# 25_-_LEDS_BUTTONS.net
KiCad netlist of a schematic drawn in Altium Designer
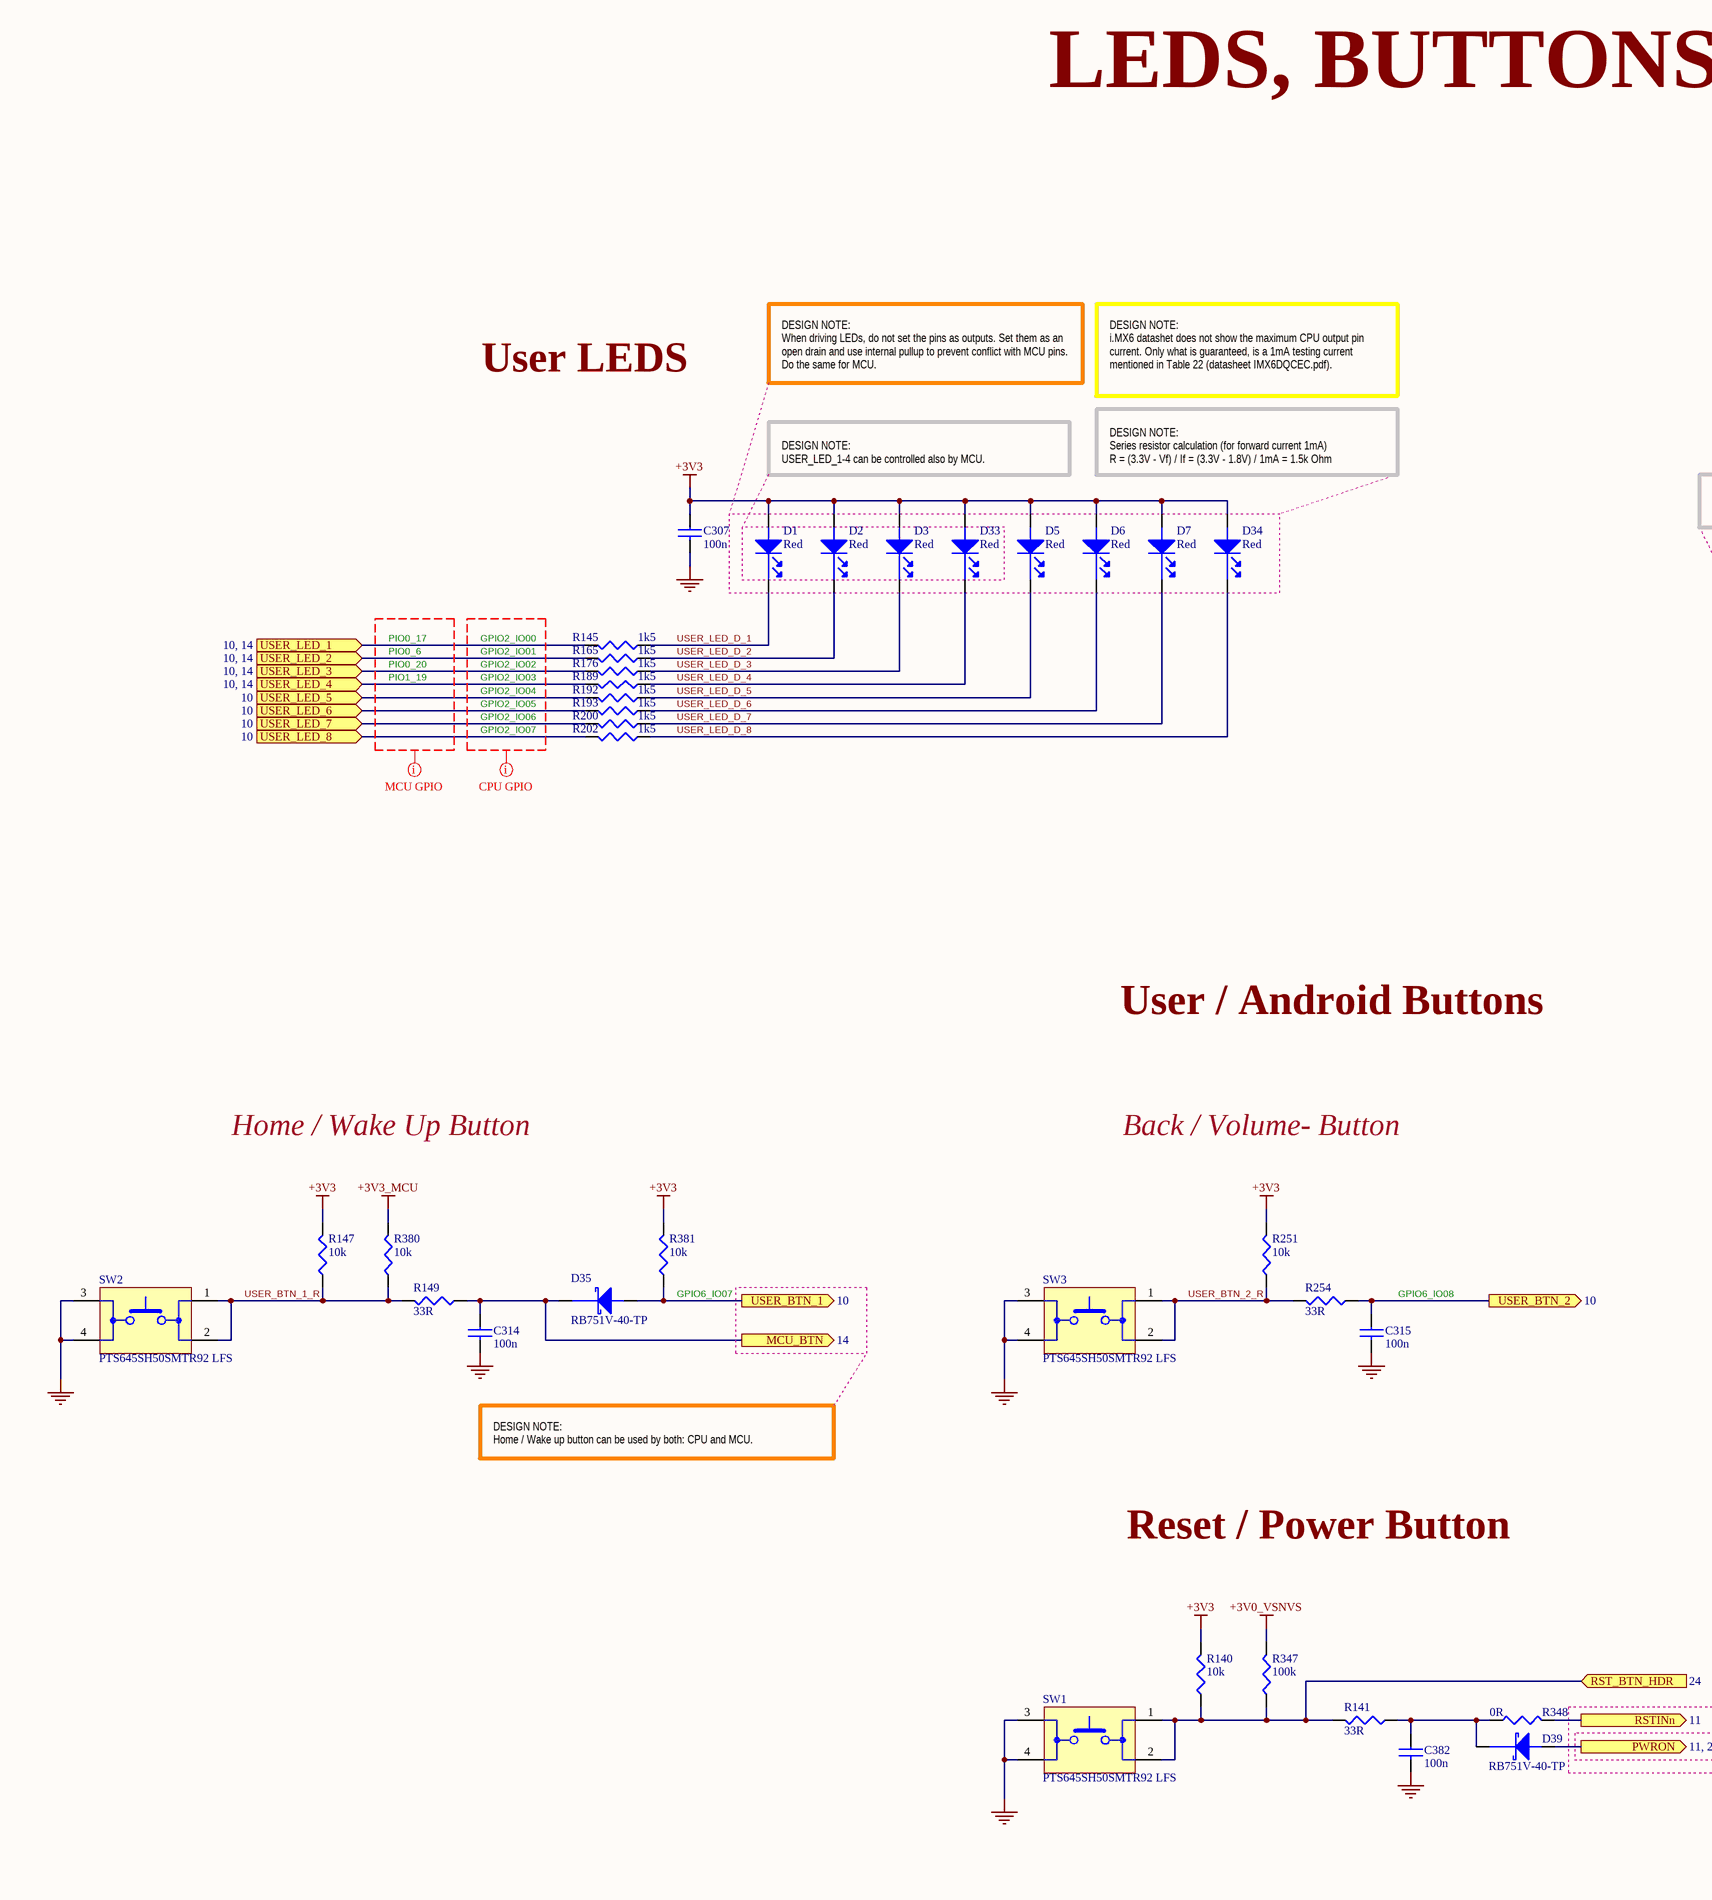
[diagram p0: [25] - LEDS, BUTTONS.SchDoc, left]
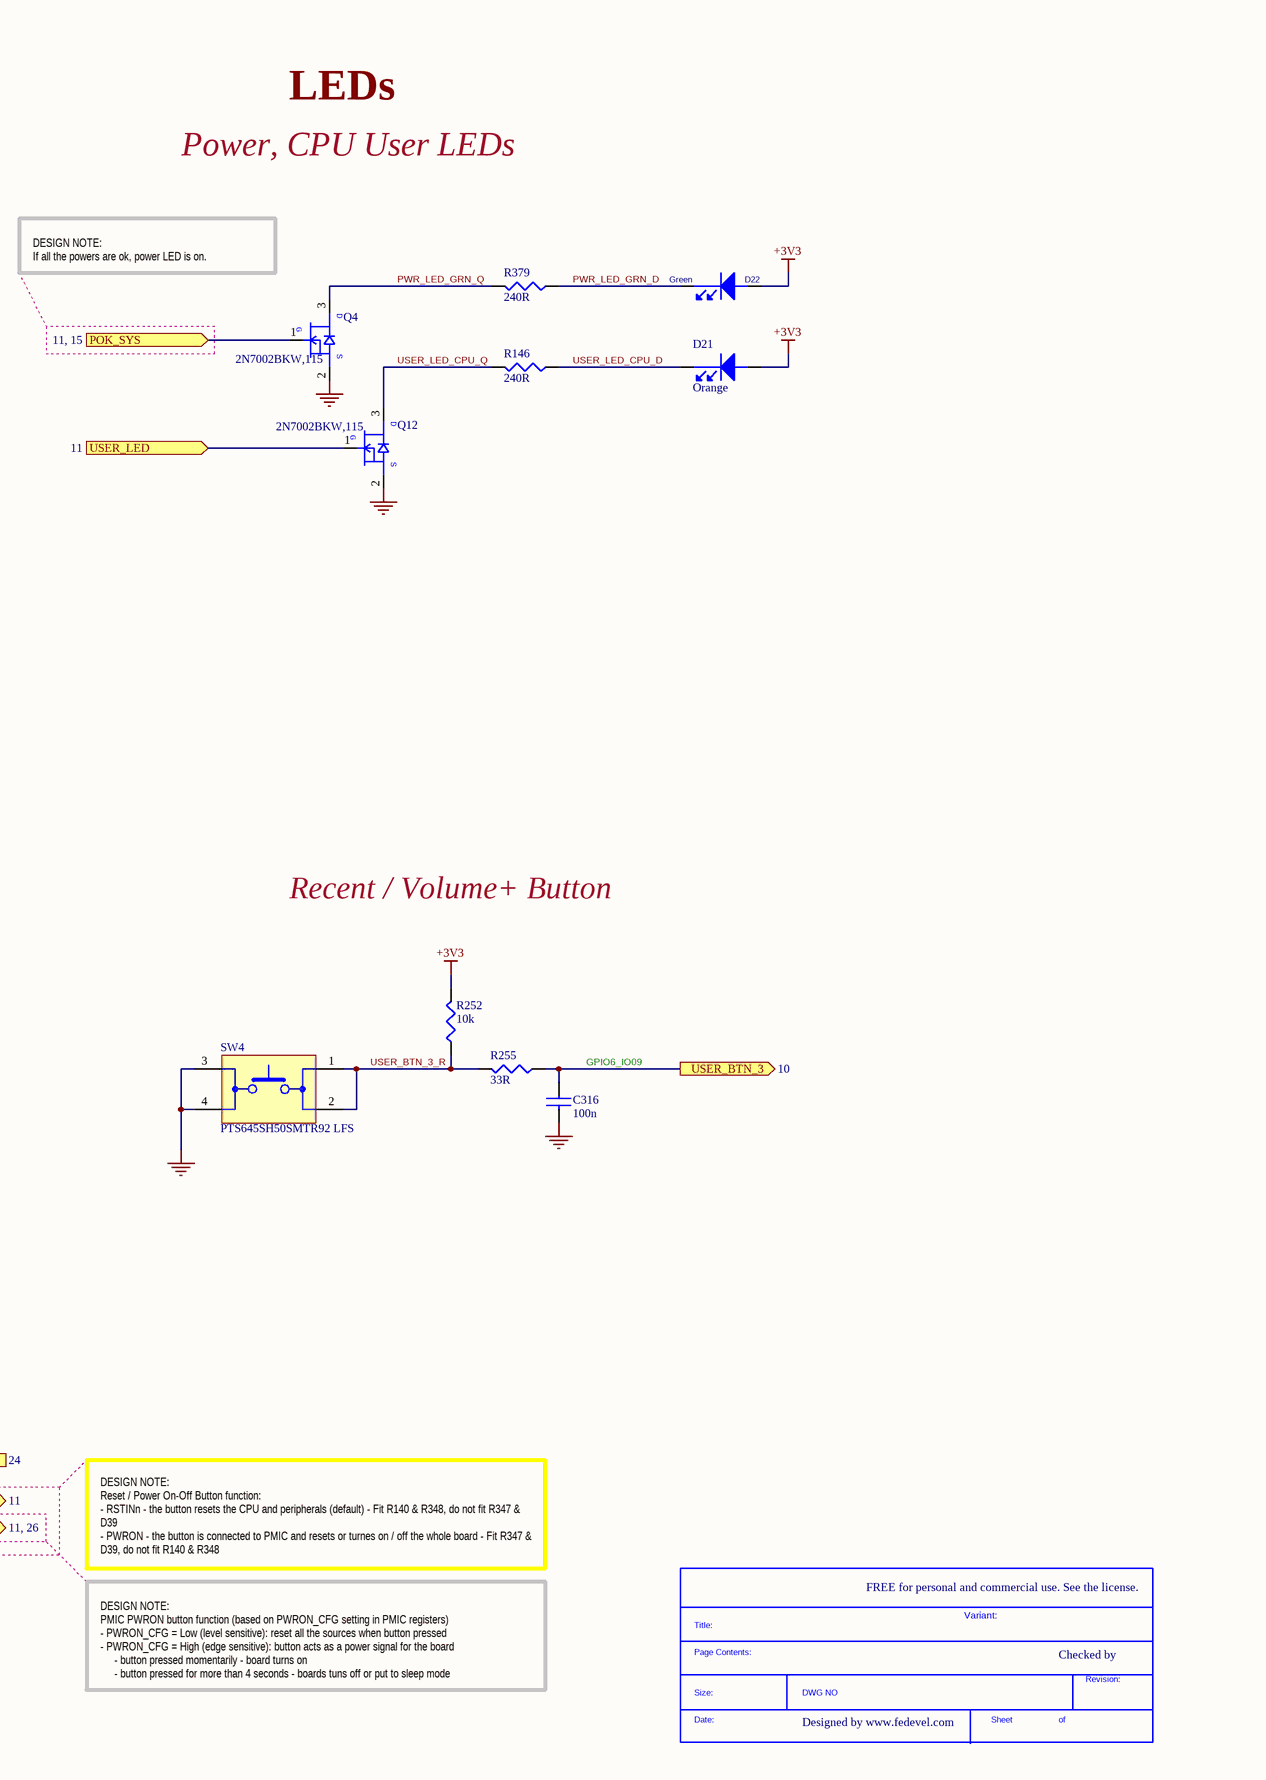
[diagram p1: [25] - LEDS, BUTTONS.SchDoc, right]

(export (version "E")
  (design (tool "Eeschema 10.0.6"))
  (components
    (comp (ref "C307")
      (value "100n")
      (footprint "C0402")
      (description "CAP CER .10UF 50V X5R 10% 0402")
      (fields
        (field (name "MANUFACTURER") "TDK Corporation")
        (field (name "MANUFACTURER PART NUMBER") "C1005X5R1H104K")
      )
      (libsource (lib "Integrated_Library_FEDEVEL_APR_2015") (part "C1005X5R1H104K"))
    )
    (comp (ref "C314")
      (value "100n")
      (footprint "C0402")
      (description "CAP CER .10UF 50V X5R 10% 0402")
      (fields
        (field (name "MANUFACTURER") "TDK Corporation")
        (field (name "MANUFACTURER PART NUMBER") "C1005X5R1H104K")
      )
      (libsource (lib "Integrated_Library_FEDEVEL_APR_2015") (part "C1005X5R1H104K"))
    )
    (comp (ref "C315")
      (value "100n")
      (footprint "C0402")
      (description "CAP CER .10UF 50V X5R 10% 0402")
      (fields
        (field (name "MANUFACTURER") "TDK Corporation")
        (field (name "MANUFACTURER PART NUMBER") "C1005X5R1H104K")
      )
      (libsource (lib "Integrated_Library_FEDEVEL_APR_2015") (part "C1005X5R1H104K"))
    )
    (comp (ref "C316")
      (value "100n")
      (footprint "C0402")
      (description "CAP CER .10UF 50V X5R 10% 0402")
      (fields
        (field (name "MANUFACTURER") "TDK Corporation")
        (field (name "MANUFACTURER PART NUMBER") "C1005X5R1H104K")
      )
      (libsource (lib "Integrated_Library_FEDEVEL_APR_2015") (part "C1005X5R1H104K"))
    )
    (comp (ref "C382")
      (value "100n")
      (footprint "C0402")
      (description "CAP CER .10UF 50V X5R 10% 0402")
      (fields
        (field (name "MANUFACTURER") "TDK Corporation")
        (field (name "MANUFACTURER PART NUMBER") "C1005X5R1H104K")
      )
      (libsource (lib "Integrated_Library_FEDEVEL_APR_2015") (part "C1005X5R1H104K"))
    )
    (comp (ref "D1")
      (value "Red")
      (footprint "LED_0603")
      (description "LED SMARTLED RED 630NM 0603 SMD")
      (fields
        (field (name "MANUFACTURER") "OSRAM Opto Semiconductors Inc")
        (field (name "MANUFACTURER PART NUMBER") "LS L29K-H1J2-1-Z")
      )
      (libsource (lib "Integrated_Library_FEDEVEL_APR_2015") (part "LS L29K-H1J2-1-Z"))
    )
    (comp (ref "D2")
      (value "Red")
      (footprint "LED_0603")
      (description "LED SMARTLED RED 630NM 0603 SMD")
      (fields
        (field (name "MANUFACTURER") "OSRAM Opto Semiconductors Inc")
        (field (name "MANUFACTURER PART NUMBER") "LS L29K-H1J2-1-Z")
      )
      (libsource (lib "Integrated_Library_FEDEVEL_APR_2015") (part "LS L29K-H1J2-1-Z"))
    )
    (comp (ref "D3")
      (value "Red")
      (footprint "LED_0603")
      (description "LED SMARTLED RED 630NM 0603 SMD")
      (fields
        (field (name "MANUFACTURER") "OSRAM Opto Semiconductors Inc")
        (field (name "MANUFACTURER PART NUMBER") "LS L29K-H1J2-1-Z")
      )
      (libsource (lib "Integrated_Library_FEDEVEL_APR_2015") (part "LS L29K-H1J2-1-Z"))
    )
    (comp (ref "D5")
      (value "Red")
      (footprint "LED_0603")
      (description "LED SMARTLED RED 630NM 0603 SMD")
      (fields
        (field (name "MANUFACTURER") "OSRAM Opto Semiconductors Inc")
        (field (name "MANUFACTURER PART NUMBER") "LS L29K-H1J2-1-Z")
      )
      (libsource (lib "Integrated_Library_FEDEVEL_APR_2015") (part "LS L29K-H1J2-1-Z"))
    )
    (comp (ref "D6")
      (value "Red")
      (footprint "LED_0603")
      (description "LED SMARTLED RED 630NM 0603 SMD")
      (fields
        (field (name "MANUFACTURER") "OSRAM Opto Semiconductors Inc")
        (field (name "MANUFACTURER PART NUMBER") "LS L29K-H1J2-1-Z")
      )
      (libsource (lib "Integrated_Library_FEDEVEL_APR_2015") (part "LS L29K-H1J2-1-Z"))
    )
    (comp (ref "D7")
      (value "Red")
      (footprint "LED_0603")
      (description "LED SMARTLED RED 630NM 0603 SMD")
      (fields
        (field (name "MANUFACTURER") "OSRAM Opto Semiconductors Inc")
        (field (name "MANUFACTURER PART NUMBER") "LS L29K-H1J2-1-Z")
      )
      (libsource (lib "Integrated_Library_FEDEVEL_APR_2015") (part "LS L29K-H1J2-1-Z"))
    )
    (comp (ref "D21")
      (value "Orange")
      (footprint "LED_0603")
      (description "LED SMARTLED ORANGE 606NM 0603")
      (fields
        (field (name "MANUFACTURER") "OSRAM Opto Semiconductors Inc")
        (field (name "MANUFACTURER PART NUMBER") "LO L29K-H2K1-24-Z")
      )
      (libsource (lib "Integrated_Library_FEDEVEL_APR_2015") (part "LO L29K-H2K1-24-Z"))
    )
    (comp (ref "D22")
      (value "Green")
      (footprint "LED_0603")
      (description "LED SMARTLED GREEN 570NM 0603")
      (fields
        (field (name "MANUFACTURER") "OSRAM Opto Semiconductors Inc")
        (field (name "MANUFACTURER PART NUMBER") "LG L29K-G2J1-24-Z")
      )
      (libsource (lib "Integrated_Library_FEDEVEL_APR_2015") (part "LG L29K-G2J1-24-Z"))
    )
    (comp (ref "D33")
      (value "Red")
      (footprint "LED_0603")
      (description "LED SMARTLED RED 630NM 0603 SMD")
      (fields
        (field (name "MANUFACTURER") "OSRAM Opto Semiconductors Inc")
        (field (name "MANUFACTURER PART NUMBER") "LS L29K-H1J2-1-Z")
      )
      (libsource (lib "Integrated_Library_FEDEVEL_APR_2015") (part "LS L29K-H1J2-1-Z"))
    )
    (comp (ref "D34")
      (value "Red")
      (footprint "LED_0603")
      (description "LED SMARTLED RED 630NM 0603 SMD")
      (fields
        (field (name "MANUFACTURER") "OSRAM Opto Semiconductors Inc")
        (field (name "MANUFACTURER PART NUMBER") "LS L29K-H1J2-1-Z")
      )
      (libsource (lib "Integrated_Library_FEDEVEL_APR_2015") (part "LS L29K-H1J2-1-Z"))
    )
    (comp (ref "D35")
      (value "RB751V-40-TP")
      (footprint "SOD323")
      (description "DIODE SCHTKY 30MA 30V SOD-323")
      (fields (field (name "MANUFACTURER") "Micro Commercial Co"))
      (libsource (lib "Integrated_Library_FEDEVEL_APR_2015") (part "RB751V-40-TP"))
    )
    (comp (ref "D39")
      (value "RB751V-40-TP")
      (footprint "SOD323")
      (description "DIODE SCHTKY 30MA 30V SOD-323")
      (fields (field (name "MANUFACTURER") "Micro Commercial Co"))
      (libsource (lib "Integrated_Library_FEDEVEL_APR_2015") (part "RB751V-40-TP"))
    )
    (comp (ref "Q4")
      (value "2N7002BKW,115")
      (footprint "SC70_SOT323")
      (description "MOSFET N-CH 60V 310MA SOT323")
      (fields (field (name "MANUFACTURER") "NXP Semiconductors"))
      (libsource (lib "Integrated_Library_FEDEVEL_APR_2015") (part "2N7002BKW,115"))
    )
    (comp (ref "Q12")
      (value "2N7002BKW,115")
      (footprint "SC70_SOT323")
      (description "MOSFET N-CH 60V 310MA SOT323")
      (fields (field (name "MANUFACTURER") "NXP Semiconductors"))
      (libsource (lib "Integrated_Library_FEDEVEL_APR_2015") (part "2N7002BKW,115"))
    )
    (comp (ref "R140")
      (value "10k")
      (footprint "R0402")
      (description "RES 10.0K OHM 1/16W 1% 0402 SMD")
      (fields
        (field (name "MANUFACTURER") "Yageo")
        (field (name "MANUFACTURER PART NUMBER") "RC0402FR-0710KL")
      )
      (libsource (lib "Integrated_Library_FEDEVEL_APR_2015") (part "RC0402FR-0710KL"))
    )
    (comp (ref "R141")
      (value "33R")
      (footprint "R0402")
      (description "RES TF 33 OHM 1% 1/16W 0402")
      (fields
        (field (name "MANUFACTURER") "Stackpole Electronics Inc")
        (field (name "MANUFACTURER PART NUMBER") "RMCF0402FT33R0")
      )
      (libsource (lib "Integrated_Library_FEDEVEL_APR_2015") (part "RMCF0402FT33R0"))
    )
    (comp (ref "R145")
      (value "1k5")
      (footprint "R0402")
      (description "RES 1.50K OHM 1/16W 1% 0402 SMD")
      (fields
        (field (name "MANUFACTURER") "Yageo")
        (field (name "MANUFACTURER PART NUMBER") "RC0402FR-071K5L")
        (field (name ".CREATOR") "MM")
        (field (name ".CHECKED PCB") "MM")
        (field (name ".CHECKED SCH") "MM")
      )
      (libsource (lib "Integrated_Library_FEDEVEL_APR_2015") (part "RC0402FR-071K5L"))
    )
    (comp (ref "R146")
      (value "240R")
      (footprint "R0402")
      (description "RES TF 240 OHM 1% 0.0625W 0402")
      (fields
        (field (name "MANUFACTURER") "Stackpole Electronics Inc")
        (field (name "MANUFACTURER PART NUMBER") "RMCF0402FT240R")
      )
      (libsource (lib "Integrated_Library_FEDEVEL_APR_2015") (part "RMCF0402FT240R"))
    )
    (comp (ref "R147")
      (value "10k")
      (footprint "R0402")
      (description "RES 10.0K OHM 1/16W 1% 0402 SMD")
      (fields
        (field (name "MANUFACTURER") "Yageo")
        (field (name "MANUFACTURER PART NUMBER") "RC0402FR-0710KL")
      )
      (libsource (lib "Integrated_Library_FEDEVEL_APR_2015") (part "RC0402FR-0710KL"))
    )
    (comp (ref "R149")
      (value "33R")
      (footprint "R0402")
      (description "RES TF 33 OHM 1% 1/16W 0402")
      (fields
        (field (name "MANUFACTURER") "Stackpole Electronics Inc")
        (field (name "MANUFACTURER PART NUMBER") "RMCF0402FT33R0")
      )
      (libsource (lib "Integrated_Library_FEDEVEL_APR_2015") (part "RMCF0402FT33R0"))
    )
    (comp (ref "R165")
      (value "1k5")
      (footprint "R0402")
      (description "RES 1.50K OHM 1/16W 1% 0402 SMD")
      (fields
        (field (name "MANUFACTURER") "Yageo")
        (field (name "MANUFACTURER PART NUMBER") "RC0402FR-071K5L")
        (field (name ".CREATOR") "MM")
        (field (name ".CHECKED PCB") "MM")
        (field (name ".CHECKED SCH") "MM")
      )
      (libsource (lib "Integrated_Library_FEDEVEL_APR_2015") (part "RC0402FR-071K5L"))
    )
    (comp (ref "R176")
      (value "1k5")
      (footprint "R0402")
      (description "RES 1.50K OHM 1/16W 1% 0402 SMD")
      (fields
        (field (name "MANUFACTURER") "Yageo")
        (field (name "MANUFACTURER PART NUMBER") "RC0402FR-071K5L")
        (field (name ".CREATOR") "MM")
        (field (name ".CHECKED PCB") "MM")
        (field (name ".CHECKED SCH") "MM")
      )
      (libsource (lib "Integrated_Library_FEDEVEL_APR_2015") (part "RC0402FR-071K5L"))
    )
    (comp (ref "R189")
      (value "1k5")
      (footprint "R0402")
      (description "RES 1.50K OHM 1/16W 1% 0402 SMD")
      (fields
        (field (name "MANUFACTURER") "Yageo")
        (field (name "MANUFACTURER PART NUMBER") "RC0402FR-071K5L")
        (field (name ".CREATOR") "MM")
        (field (name ".CHECKED PCB") "MM")
        (field (name ".CHECKED SCH") "MM")
      )
      (libsource (lib "Integrated_Library_FEDEVEL_APR_2015") (part "RC0402FR-071K5L"))
    )
    (comp (ref "R192")
      (value "1k5")
      (footprint "R0402")
      (description "RES 1.50K OHM 1/16W 1% 0402 SMD")
      (fields
        (field (name "MANUFACTURER") "Yageo")
        (field (name "MANUFACTURER PART NUMBER") "RC0402FR-071K5L")
        (field (name ".CREATOR") "MM")
        (field (name ".CHECKED PCB") "MM")
        (field (name ".CHECKED SCH") "MM")
      )
      (libsource (lib "Integrated_Library_FEDEVEL_APR_2015") (part "RC0402FR-071K5L"))
    )
    (comp (ref "R193")
      (value "1k5")
      (footprint "R0402")
      (description "RES 1.50K OHM 1/16W 1% 0402 SMD")
      (fields
        (field (name "MANUFACTURER") "Yageo")
        (field (name "MANUFACTURER PART NUMBER") "RC0402FR-071K5L")
        (field (name ".CREATOR") "MM")
        (field (name ".CHECKED PCB") "MM")
        (field (name ".CHECKED SCH") "MM")
      )
      (libsource (lib "Integrated_Library_FEDEVEL_APR_2015") (part "RC0402FR-071K5L"))
    )
    (comp (ref "R200")
      (value "1k5")
      (footprint "R0402")
      (description "RES 1.50K OHM 1/16W 1% 0402 SMD")
      (fields
        (field (name "MANUFACTURER") "Yageo")
        (field (name "MANUFACTURER PART NUMBER") "RC0402FR-071K5L")
        (field (name ".CREATOR") "MM")
        (field (name ".CHECKED PCB") "MM")
        (field (name ".CHECKED SCH") "MM")
      )
      (libsource (lib "Integrated_Library_FEDEVEL_APR_2015") (part "RC0402FR-071K5L"))
    )
    (comp (ref "R202")
      (value "1k5")
      (footprint "R0402")
      (description "RES 1.50K OHM 1/16W 1% 0402 SMD")
      (fields
        (field (name "MANUFACTURER") "Yageo")
        (field (name "MANUFACTURER PART NUMBER") "RC0402FR-071K5L")
        (field (name ".CREATOR") "MM")
        (field (name ".CHECKED PCB") "MM")
        (field (name ".CHECKED SCH") "MM")
      )
      (libsource (lib "Integrated_Library_FEDEVEL_APR_2015") (part "RC0402FR-071K5L"))
    )
    (comp (ref "R251")
      (value "10k")
      (footprint "R0402")
      (description "RES 10.0K OHM 1/16W 1% 0402 SMD")
      (fields
        (field (name "MANUFACTURER") "Yageo")
        (field (name "MANUFACTURER PART NUMBER") "RC0402FR-0710KL")
      )
      (libsource (lib "Integrated_Library_FEDEVEL_APR_2015") (part "RC0402FR-0710KL"))
    )
    (comp (ref "R252")
      (value "10k")
      (footprint "R0402")
      (description "RES 10.0K OHM 1/16W 1% 0402 SMD")
      (fields
        (field (name "MANUFACTURER") "Yageo")
        (field (name "MANUFACTURER PART NUMBER") "RC0402FR-0710KL")
      )
      (libsource (lib "Integrated_Library_FEDEVEL_APR_2015") (part "RC0402FR-0710KL"))
    )
    (comp (ref "R254")
      (value "33R")
      (footprint "R0402")
      (description "RES TF 33 OHM 1% 1/16W 0402")
      (fields
        (field (name "MANUFACTURER") "Stackpole Electronics Inc")
        (field (name "MANUFACTURER PART NUMBER") "RMCF0402FT33R0")
      )
      (libsource (lib "Integrated_Library_FEDEVEL_APR_2015") (part "RMCF0402FT33R0"))
    )
    (comp (ref "R255")
      (value "33R")
      (footprint "R0402")
      (description "RES TF 33 OHM 1% 1/16W 0402")
      (fields
        (field (name "MANUFACTURER") "Stackpole Electronics Inc")
        (field (name "MANUFACTURER PART NUMBER") "RMCF0402FT33R0")
      )
      (libsource (lib "Integrated_Library_FEDEVEL_APR_2015") (part "RMCF0402FT33R0"))
    )
    (comp (ref "R347")
      (value "100k")
      (footprint "R0402")
      (description "RES 100K OHM 1/16W 1% 0402 SMD")
      (fields
        (field (name "MANUFACTURER") "Stackpole Electronics Inc")
        (field (name "MANUFACTURER PART NUMBER") "RMCF0402FT100K")
      )
      (libsource (lib "Integrated_Library_FEDEVEL_APR_2015") (part "RMCF0402FT100K"))
    )
    (comp (ref "R348")
      (value "0R")
      (footprint "R0402")
      (description "RES 0.0 OHM 1/16W 0402 SMD")
      (fields
        (field (name "MANUFACTURER") "Yageo")
        (field (name "MANUFACTURER PART NUMBER") "RC0402JR-070RL")
      )
      (libsource (lib "Integrated_Library_FEDEVEL_APR_2015") (part "RC0402JR-070RL"))
    )
    (comp (ref "R379")
      (value "240R")
      (footprint "R0402")
      (description "RES TF 240 OHM 1% 0.0625W 0402")
      (fields
        (field (name "MANUFACTURER") "Stackpole Electronics Inc")
        (field (name "MANUFACTURER PART NUMBER") "RMCF0402FT240R")
      )
      (libsource (lib "Integrated_Library_FEDEVEL_APR_2015") (part "RMCF0402FT240R"))
    )
    (comp (ref "R380")
      (value "10k")
      (footprint "R0402")
      (description "RES 10.0K OHM 1/16W 1% 0402 SMD")
      (fields
        (field (name "MANUFACTURER") "Yageo")
        (field (name "MANUFACTURER PART NUMBER") "RC0402FR-0710KL")
      )
      (libsource (lib "Integrated_Library_FEDEVEL_APR_2015") (part "RC0402FR-0710KL"))
    )
    (comp (ref "R381")
      (value "10k")
      (footprint "R0402")
      (description "RES 10.0K OHM 1/16W 1% 0402 SMD")
      (fields
        (field (name "MANUFACTURER") "Yageo")
        (field (name "MANUFACTURER PART NUMBER") "RC0402FR-0710KL")
      )
      (libsource (lib "Integrated_Library_FEDEVEL_APR_2015") (part "RC0402FR-0710KL"))
    )
    (comp (ref "SW1")
      (value "PTS645SH50SMTR92 LFS")
      (footprint "TACT_SMD")
      (description "SWITCH TACTILE SPST-NO 0.05A 12V")
      (fields
        (field (name "MANUFACTURER") "C&K Components")
        (field (name ".CHECKED PCB") "MM")
        (field (name ".CHECKED SCH") "MM")
        (field (name ".CREATOR") "MM")
      )
      (libsource (lib "Integrated_Library_FEDEVEL_APR_2015") (part "PTS645SH50SMTR92 LFS"))
    )
    (comp (ref "SW2")
      (value "PTS645SH50SMTR92 LFS")
      (footprint "TACT_SMD")
      (description "SWITCH TACTILE SPST-NO 0.05A 12V")
      (fields
        (field (name "MANUFACTURER") "C&K Components")
        (field (name ".CHECKED PCB") "MM")
        (field (name ".CHECKED SCH") "MM")
        (field (name ".CREATOR") "MM")
      )
      (libsource (lib "Integrated_Library_FEDEVEL_APR_2015") (part "PTS645SH50SMTR92 LFS"))
    )
    (comp (ref "SW3")
      (value "PTS645SH50SMTR92 LFS")
      (footprint "TACT_SMD")
      (description "SWITCH TACTILE SPST-NO 0.05A 12V")
      (fields
        (field (name "MANUFACTURER") "C&K Components")
        (field (name ".CHECKED PCB") "MM")
        (field (name ".CHECKED SCH") "MM")
        (field (name ".CREATOR") "MM")
      )
      (libsource (lib "Integrated_Library_FEDEVEL_APR_2015") (part "PTS645SH50SMTR92 LFS"))
    )
    (comp (ref "SW4")
      (value "PTS645SH50SMTR92 LFS")
      (footprint "TACT_SMD")
      (description "SWITCH TACTILE SPST-NO 0.05A 12V")
      (fields
        (field (name "MANUFACTURER") "C&K Components")
        (field (name ".CHECKED PCB") "MM")
        (field (name ".CHECKED SCH") "MM")
        (field (name ".CREATOR") "MM")
      )
      (libsource (lib "Integrated_Library_FEDEVEL_APR_2015") (part "PTS645SH50SMTR92 LFS"))
    )
  )
  (nets
    (net (code "1") (name "+3V0_VSNVS") (class "Default")
      (node (ref "R347") (pin "2") (pinfunction "2_2") (pintype "passive"))
    )
    (net (code "2") (name "+3V3") (class "Default")
      (node (ref "C307") (pin "1") (pinfunction "1_1") (pintype "passive"))
      (node (ref "D1") (pin "2") (pinfunction "ANODE_2") (pintype "passive"))
      (node (ref "D2") (pin "2") (pinfunction "ANODE_2") (pintype "passive"))
      (node (ref "D21") (pin "2") (pinfunction "ANODE_2") (pintype "passive"))
      (node (ref "D22") (pin "2") (pinfunction "ANODE_2") (pintype "passive"))
      (node (ref "D3") (pin "2") (pinfunction "ANODE_2") (pintype "passive"))
      (node (ref "D33") (pin "2") (pinfunction "ANODE_2") (pintype "passive"))
      (node (ref "D34") (pin "2") (pinfunction "ANODE_2") (pintype "passive"))
      (node (ref "D5") (pin "2") (pinfunction "ANODE_2") (pintype "passive"))
      (node (ref "D6") (pin "2") (pinfunction "ANODE_2") (pintype "passive"))
      (node (ref "D7") (pin "2") (pinfunction "ANODE_2") (pintype "passive"))
      (node (ref "R140") (pin "2") (pinfunction "2_2") (pintype "passive"))
      (node (ref "R147") (pin "2") (pinfunction "2_2") (pintype "passive"))
      (node (ref "R251") (pin "2") (pinfunction "2_2") (pintype "passive"))
      (node (ref "R252") (pin "2") (pinfunction "2_2") (pintype "passive"))
      (node (ref "R381") (pin "2") (pinfunction "2_2") (pintype "passive"))
    )
    (net (code "3") (name "+3V3_MCU") (class "Default")
      (node (ref "R380") (pin "2") (pinfunction "2_2") (pintype "passive"))
    )
    (net (code "4") (name "/MCU_BTN") (class "Default")
      (node (ref "C314") (pin "1") (pinfunction "1_1") (pintype "passive"))
      (node (ref "D35") (pin "1") (pinfunction "cathode_1") (pintype "passive"))
      (node (ref "R149") (pin "1") (pinfunction "1_1") (pintype "passive"))
    )
    (net (code "5") (name "/POK_SYS") (class "Default")
      (node (ref "Q4") (pin "1") (pinfunction "GATE_1") (pintype "passive"))
    )
    (net (code "6") (name "/PWRON") (class "Default")
      (node (ref "D39") (pin "2") (pinfunction "ANODE_2") (pintype "passive"))
    )
    (net (code "7") (name "/PWR_LED_GRN_D") (class "Default")
      (node (ref "D22") (pin "1") (pinfunction "cathode_1") (pintype "passive"))
      (node (ref "R379") (pin "1") (pinfunction "1_1") (pintype "passive"))
    )
    (net (code "8") (name "/PWR_LED_GRN_Q") (class "Default")
      (node (ref "Q4") (pin "3") (pinfunction "DRAIN_3") (pintype "passive"))
      (node (ref "R379") (pin "2") (pinfunction "2_2") (pintype "passive"))
    )
    (net (code "9") (name "/RSTINn") (class "Default")
      (node (ref "R348") (pin "2") (pinfunction "2_2") (pintype "passive"))
    )
    (net (code "10") (name "/RST_BTN_HDR") (class "Default")
      (node (ref "R140") (pin "1") (pinfunction "1_1") (pintype "passive"))
      (node (ref "R141") (pin "2") (pinfunction "2_2") (pintype "passive"))
      (node (ref "R347") (pin "1") (pinfunction "1_1") (pintype "passive"))
      (node (ref "SW1") (pin "1") (pinfunction "1_1") (pintype "passive"))
      (node (ref "SW1") (pin "2") (pinfunction "2_2") (pintype "passive"))
    )
    (net (code "11") (name "/USER_BTN_1") (class "Default")
      (node (ref "D35") (pin "2") (pinfunction "ANODE_2") (pintype "passive"))
      (node (ref "R381") (pin "1") (pinfunction "1_1") (pintype "passive"))
    )
    (net (code "12") (name "/USER_BTN_1_R") (class "Default")
      (node (ref "R147") (pin "1") (pinfunction "1_1") (pintype "passive"))
      (node (ref "R149") (pin "2") (pinfunction "2_2") (pintype "passive"))
      (node (ref "R380") (pin "1") (pinfunction "1_1") (pintype "passive"))
      (node (ref "SW2") (pin "1") (pinfunction "1_1") (pintype "passive"))
      (node (ref "SW2") (pin "2") (pinfunction "2_2") (pintype "passive"))
    )
    (net (code "13") (name "/USER_BTN_2") (class "Default")
      (node (ref "C315") (pin "1") (pinfunction "1_1") (pintype "passive"))
      (node (ref "R254") (pin "1") (pinfunction "1_1") (pintype "passive"))
    )
    (net (code "14") (name "/USER_BTN_2_R") (class "Default")
      (node (ref "R251") (pin "1") (pinfunction "1_1") (pintype "passive"))
      (node (ref "R254") (pin "2") (pinfunction "2_2") (pintype "passive"))
      (node (ref "SW3") (pin "1") (pinfunction "1_1") (pintype "passive"))
      (node (ref "SW3") (pin "2") (pinfunction "2_2") (pintype "passive"))
    )
    (net (code "15") (name "/USER_BTN_3") (class "Default")
      (node (ref "C316") (pin "1") (pinfunction "1_1") (pintype "passive"))
      (node (ref "R255") (pin "1") (pinfunction "1_1") (pintype "passive"))
    )
    (net (code "16") (name "/USER_BTN_3_R") (class "Default")
      (node (ref "R252") (pin "1") (pinfunction "1_1") (pintype "passive"))
      (node (ref "R255") (pin "2") (pinfunction "2_2") (pintype "passive"))
      (node (ref "SW4") (pin "1") (pinfunction "1_1") (pintype "passive"))
      (node (ref "SW4") (pin "2") (pinfunction "2_2") (pintype "passive"))
    )
    (net (code "17") (name "/USER_LED") (class "Default")
      (node (ref "Q12") (pin "1") (pinfunction "GATE_1") (pintype "passive"))
    )
    (net (code "18") (name "/USER_LED_1") (class "Default")
      (node (ref "R145") (pin "2") (pinfunction "2_2") (pintype "passive"))
    )
    (net (code "19") (name "/USER_LED_2") (class "Default")
      (node (ref "R165") (pin "2") (pinfunction "2_2") (pintype "passive"))
    )
    (net (code "20") (name "/USER_LED_3") (class "Default")
      (node (ref "R176") (pin "2") (pinfunction "2_2") (pintype "passive"))
    )
    (net (code "21") (name "/USER_LED_4") (class "Default")
      (node (ref "R189") (pin "2") (pinfunction "2_2") (pintype "passive"))
    )
    (net (code "22") (name "/USER_LED_5") (class "Default")
      (node (ref "R192") (pin "2") (pinfunction "2_2") (pintype "passive"))
    )
    (net (code "23") (name "/USER_LED_6") (class "Default")
      (node (ref "R193") (pin "2") (pinfunction "2_2") (pintype "passive"))
    )
    (net (code "24") (name "/USER_LED_7") (class "Default")
      (node (ref "R200") (pin "2") (pinfunction "2_2") (pintype "passive"))
    )
    (net (code "25") (name "/USER_LED_8") (class "Default")
      (node (ref "R202") (pin "2") (pinfunction "2_2") (pintype "passive"))
    )
    (net (code "26") (name "/USER_LED_CPU_D") (class "Default")
      (node (ref "D21") (pin "1") (pinfunction "cathode_1") (pintype "passive"))
      (node (ref "R146") (pin "1") (pinfunction "1_1") (pintype "passive"))
    )
    (net (code "27") (name "/USER_LED_CPU_Q") (class "Default")
      (node (ref "Q12") (pin "3") (pinfunction "DRAIN_3") (pintype "passive"))
      (node (ref "R146") (pin "2") (pinfunction "2_2") (pintype "passive"))
    )
    (net (code "28") (name "/USER_LED_D_1") (class "Default")
      (node (ref "D1") (pin "1") (pinfunction "cathode_1") (pintype "passive"))
      (node (ref "R145") (pin "1") (pinfunction "1_1") (pintype "passive"))
    )
    (net (code "29") (name "/USER_LED_D_2") (class "Default")
      (node (ref "D2") (pin "1") (pinfunction "cathode_1") (pintype "passive"))
      (node (ref "R165") (pin "1") (pinfunction "1_1") (pintype "passive"))
    )
    (net (code "30") (name "/USER_LED_D_3") (class "Default")
      (node (ref "D3") (pin "1") (pinfunction "cathode_1") (pintype "passive"))
      (node (ref "R176") (pin "1") (pinfunction "1_1") (pintype "passive"))
    )
    (net (code "31") (name "/USER_LED_D_4") (class "Default")
      (node (ref "D33") (pin "1") (pinfunction "cathode_1") (pintype "passive"))
      (node (ref "R189") (pin "1") (pinfunction "1_1") (pintype "passive"))
    )
    (net (code "32") (name "/USER_LED_D_5") (class "Default")
      (node (ref "D5") (pin "1") (pinfunction "cathode_1") (pintype "passive"))
      (node (ref "R192") (pin "1") (pinfunction "1_1") (pintype "passive"))
    )
    (net (code "33") (name "/USER_LED_D_6") (class "Default")
      (node (ref "D6") (pin "1") (pinfunction "cathode_1") (pintype "passive"))
      (node (ref "R193") (pin "1") (pinfunction "1_1") (pintype "passive"))
    )
    (net (code "34") (name "/USER_LED_D_7") (class "Default")
      (node (ref "D7") (pin "1") (pinfunction "cathode_1") (pintype "passive"))
      (node (ref "R200") (pin "1") (pinfunction "1_1") (pintype "passive"))
    )
    (net (code "35") (name "/USER_LED_D_8") (class "Default")
      (node (ref "D34") (pin "1") (pinfunction "cathode_1") (pintype "passive"))
      (node (ref "R202") (pin "1") (pinfunction "1_1") (pintype "passive"))
    )
    (net (code "36") (name "GND") (class "Default")
      (node (ref "C307") (pin "2") (pinfunction "2_2") (pintype "passive"))
      (node (ref "C314") (pin "2") (pinfunction "2_2") (pintype "passive"))
      (node (ref "C315") (pin "2") (pinfunction "2_2") (pintype "passive"))
      (node (ref "C316") (pin "2") (pinfunction "2_2") (pintype "passive"))
      (node (ref "C382") (pin "2") (pinfunction "2_2") (pintype "passive"))
      (node (ref "Q12") (pin "2") (pinfunction "SOURCE_2") (pintype "passive"))
      (node (ref "Q4") (pin "2") (pinfunction "SOURCE_2") (pintype "passive"))
      (node (ref "SW1") (pin "3") (pinfunction "MECH1_3") (pintype "passive"))
      (node (ref "SW1") (pin "4") (pinfunction "MECH2_4") (pintype "passive"))
      (node (ref "SW2") (pin "3") (pinfunction "MECH1_3") (pintype "passive"))
      (node (ref "SW2") (pin "4") (pinfunction "MECH2_4") (pintype "passive"))
      (node (ref "SW3") (pin "3") (pinfunction "MECH1_3") (pintype "passive"))
      (node (ref "SW3") (pin "4") (pinfunction "MECH2_4") (pintype "passive"))
      (node (ref "SW4") (pin "3") (pinfunction "MECH1_3") (pintype "passive"))
      (node (ref "SW4") (pin "4") (pinfunction "MECH2_4") (pintype "passive"))
    )
    (net (code "37") (name "Net-(D39-cathode)") (class "Default")
      (node (ref "C382") (pin "1") (pinfunction "1_1") (pintype "passive"))
      (node (ref "D39") (pin "1") (pinfunction "cathode_1") (pintype "passive"))
      (node (ref "R141") (pin "1") (pinfunction "1_1") (pintype "passive"))
      (node (ref "R348") (pin "1") (pinfunction "1_1") (pintype "passive"))
    )
  )
)
